# top_level.net
KiCad netlist of a schematic drawn in Altium Designer
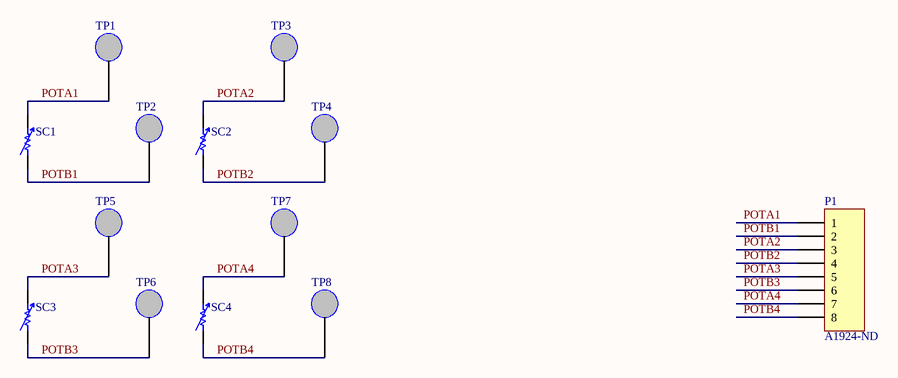
[diagram p0: top_level.SchDoc]

(export (version "E")
  (design (tool "Eeschema 10.0.6"))
  (components
    (comp (ref "P1")
      (value "CON - HEADER 1X8")
      (footprint "CON-HEADER-1X8")
      (description "100mil header 1 row 6 pins")
      (fields (field (name "SUPPLIER PART NUMBER 1") "A1924-ND"))
      (libsource (lib "CHINOOK_LIBRARY") (part "CON - HEADER 1X8"))
    )
    (comp (ref "SC1")
      (value "RS - RESISTOR VARIABLE")
      (footprint "SC - KXOB22-04X3L")
      (fields (field (name "TOLERANCE") "RES TOL") (field (name "POWER") "RES POWER"))
      (libsource (lib "CHINOOK_LIBRARY") (part "RS - RESISTOR VARIABLE"))
    )
    (comp (ref "SC2")
      (value "RS - RESISTOR VARIABLE")
      (footprint "SC - KXOB22-04X3L")
      (fields (field (name "TOLERANCE") "RES TOL") (field (name "POWER") "RES POWER"))
      (libsource (lib "CHINOOK_LIBRARY") (part "RS - RESISTOR VARIABLE"))
    )
    (comp (ref "SC3")
      (value "RS - RESISTOR VARIABLE")
      (footprint "SC - KXOB22-04X3L")
      (fields (field (name "TOLERANCE") "RES TOL") (field (name "POWER") "RES POWER"))
      (libsource (lib "CHINOOK_LIBRARY") (part "RS - RESISTOR VARIABLE"))
    )
    (comp (ref "SC4")
      (value "RS - RESISTOR VARIABLE")
      (footprint "SC - KXOB22-04X3L")
      (fields (field (name "TOLERANCE") "RES TOL") (field (name "POWER") "RES POWER"))
      (libsource (lib "CHINOOK_LIBRARY") (part "RS - RESISTOR VARIABLE"))
    )
    (comp (ref "TP1")
      (value "5003K")
      (footprint "TP - VERTICAL")
      (libsource (lib "CHINOOK_LIBRARY") (part "TP - Test point vertical"))
    )
    (comp (ref "TP2")
      (value "5003K")
      (footprint "TP - VERTICAL")
      (libsource (lib "CHINOOK_LIBRARY") (part "TP - Test point vertical"))
    )
    (comp (ref "TP3")
      (value "5003K")
      (footprint "TP - VERTICAL")
      (libsource (lib "CHINOOK_LIBRARY") (part "TP - Test point vertical"))
    )
    (comp (ref "TP4")
      (value "5003K")
      (footprint "TP - VERTICAL")
      (libsource (lib "CHINOOK_LIBRARY") (part "TP - Test point vertical"))
    )
    (comp (ref "TP5")
      (value "5003K")
      (footprint "TP - VERTICAL")
      (libsource (lib "CHINOOK_LIBRARY") (part "TP - Test point vertical"))
    )
    (comp (ref "TP6")
      (value "5003K")
      (footprint "TP - VERTICAL")
      (libsource (lib "CHINOOK_LIBRARY") (part "TP - Test point vertical"))
    )
    (comp (ref "TP7")
      (value "5003K")
      (footprint "TP - VERTICAL")
      (libsource (lib "CHINOOK_LIBRARY") (part "TP - Test point vertical"))
    )
    (comp (ref "TP8")
      (value "5003K")
      (footprint "TP - VERTICAL")
      (libsource (lib "CHINOOK_LIBRARY") (part "TP - Test point vertical"))
    )
  )
  (nets
    (net (code "1") (name "/POTA1") (class "Default")
      (node (ref "P1") (pin "1") (pinfunction "1_1") (pintype "passive"))
      (node (ref "SC1") (pin "2") (pinfunction "2_2") (pintype "passive"))
      (node (ref "TP1") (pin "1") (pinfunction "1_1") (pintype "passive"))
    )
    (net (code "2") (name "/POTA2") (class "Default")
      (node (ref "P1") (pin "3") (pinfunction "3_3") (pintype "passive"))
      (node (ref "SC2") (pin "2") (pinfunction "2_2") (pintype "passive"))
      (node (ref "TP3") (pin "1") (pinfunction "1_1") (pintype "passive"))
    )
    (net (code "3") (name "/POTA3") (class "Default")
      (node (ref "P1") (pin "5") (pinfunction "5_5") (pintype "passive"))
      (node (ref "SC3") (pin "2") (pinfunction "2_2") (pintype "passive"))
      (node (ref "TP5") (pin "1") (pinfunction "1_1") (pintype "passive"))
    )
    (net (code "4") (name "/POTA4") (class "Default")
      (node (ref "P1") (pin "7") (pinfunction "7_7") (pintype "passive"))
      (node (ref "SC4") (pin "2") (pinfunction "2_2") (pintype "passive"))
      (node (ref "TP7") (pin "1") (pinfunction "1_1") (pintype "passive"))
    )
    (net (code "5") (name "/POTB1") (class "Default")
      (node (ref "P1") (pin "2") (pinfunction "2_2") (pintype "passive"))
      (node (ref "SC1") (pin "1") (pinfunction "1_1") (pintype "passive"))
      (node (ref "TP2") (pin "1") (pinfunction "1_1") (pintype "passive"))
    )
    (net (code "6") (name "/POTB2") (class "Default")
      (node (ref "P1") (pin "4") (pinfunction "4_4") (pintype "passive"))
      (node (ref "SC2") (pin "1") (pinfunction "1_1") (pintype "passive"))
      (node (ref "TP4") (pin "1") (pinfunction "1_1") (pintype "passive"))
    )
    (net (code "7") (name "/POTB3") (class "Default")
      (node (ref "P1") (pin "6") (pinfunction "6_6") (pintype "passive"))
      (node (ref "SC3") (pin "1") (pinfunction "1_1") (pintype "passive"))
      (node (ref "TP6") (pin "1") (pinfunction "1_1") (pintype "passive"))
    )
    (net (code "8") (name "/POTB4") (class "Default")
      (node (ref "P1") (pin "8") (pinfunction "8_8") (pintype "passive"))
      (node (ref "SC4") (pin "1") (pinfunction "1_1") (pintype "passive"))
      (node (ref "TP8") (pin "1") (pinfunction "1_1") (pintype "passive"))
    )
  )
)
